# LD_DRV_CK.net
KiCad netlist of a schematic drawn in EAGLE
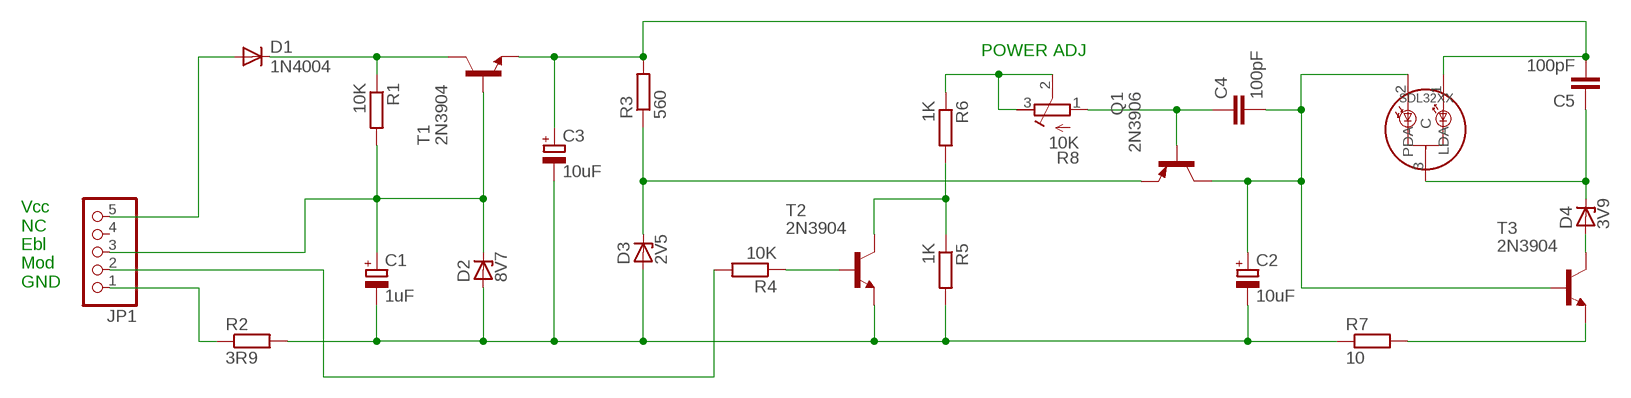
[diagram p0: schematic, sheet 1]

(export (version "E")
  (design (tool "Eeschema 10.0.6"))
  (components
    (comp (ref "C1")
      (value "1uF")
      (footprint "eagle-import:E2,5-6E")
      (libsource (lib "eagle-import") (part "CPOL-EUE2,5-6E"))
    )
    (comp (ref "C2")
      (value "10uF")
      (footprint "eagle-import:E2,5-6E")
      (libsource (lib "eagle-import") (part "CPOL-EUE2,5-6E"))
    )
    (comp (ref "C3")
      (value "10uF")
      (footprint "eagle-import:E2,5-6E")
      (libsource (lib "eagle-import") (part "CPOL-EUE2,5-6E"))
    )
    (comp (ref "C4")
      (value "100pF")
      (footprint "eagle-import:C025-030X050")
      (libsource (lib "eagle-import") (part "C-EU025-030X050"))
    )
    (comp (ref "C5")
      (value "100pF")
      (footprint "eagle-import:C025-030X050")
      (libsource (lib "eagle-import") (part "C-EU025-030X050"))
    )
    (comp (ref "D1")
      (value "1N4004")
      (footprint "eagle-import:DO41-10")
      (libsource (lib "eagle-import") (part "1N4004"))
    )
    (comp (ref "D2")
      (value "8V7")
      (footprint "eagle-import:ZDIO-10")
      (libsource (lib "eagle-import") (part "ZENER-DIODEZD-10"))
    )
    (comp (ref "D3")
      (value "2V5")
      (footprint "eagle-import:ZDIO-10")
      (libsource (lib "eagle-import") (part "ZENER-DIODEZD-10"))
    )
    (comp (ref "D4")
      (value "3V9")
      (footprint "eagle-import:ZDIO-10")
      (libsource (lib "eagle-import") (part "ZENER-DIODEZD-10"))
    )
    (comp (ref "JP1")
      (value "PINHD-1X5/90")
      (footprint "eagle-import:1X05_90")
      (libsource (lib "eagle-import") (part "PINHD-1X5/90"))
    )
    (comp (ref "Q1")
      (value "2N3906")
      (footprint "eagle-import:TO92")
      (libsource (lib "eagle-import") (part "2N3906"))
    )
    (comp (ref "R1")
      (value "10K")
      (footprint "eagle-import:0207_10")
      (libsource (lib "eagle-import") (part "R-EU_0207/10"))
    )
    (comp (ref "R2")
      (value "3R9")
      (footprint "eagle-import:0207_10")
      (libsource (lib "eagle-import") (part "R-EU_0207/10"))
    )
    (comp (ref "R3")
      (value "560")
      (footprint "eagle-import:0207_10")
      (libsource (lib "eagle-import") (part "R-EU_0207/10"))
    )
    (comp (ref "R4")
      (value "10K")
      (footprint "eagle-import:0207_10")
      (libsource (lib "eagle-import") (part "R-EU_0207/10"))
    )
    (comp (ref "R5")
      (value "1K")
      (footprint "eagle-import:0207_10")
      (libsource (lib "eagle-import") (part "R-EU_0207/10"))
    )
    (comp (ref "R6")
      (value "1K")
      (footprint "eagle-import:0207_10")
      (libsource (lib "eagle-import") (part "R-EU_0207/10"))
    )
    (comp (ref "R7")
      (value "10")
      (footprint "eagle-import:0207_10")
      (libsource (lib "eagle-import") (part "R-EU_0207/10"))
    )
    (comp (ref "R8")
      (value "10K")
      (footprint "eagle-import:RTRIM3339P")
      (libsource (lib "eagle-import") (part "R-TRIMM3339P"))
    )
    (comp (ref "SLD32XX_1")
      (value "SLD32XX")
      (footprint "eagle-import:SLD32XXVF")
      (libsource (lib "eagle-import") (part "SLD32XX"))
    )
    (comp (ref "T1")
      (value "2N3904")
      (footprint "eagle-import:TO92")
      (libsource (lib "eagle-import") (part "2N3904"))
    )
    (comp (ref "T2")
      (value "2N3904")
      (footprint "eagle-import:TO92")
      (libsource (lib "eagle-import") (part "2N3904"))
    )
    (comp (ref "T3")
      (value "2N3904")
      (footprint "eagle-import:TO92")
      (libsource (lib "eagle-import") (part "2N3904"))
    )
  )
  (nets
    (net (code "1") (name "Net-(D1-PadA)") (class "Default")
      (node (ref "D1") (pin "A") (pinfunction "A_A") (pintype "passive"))
      (node (ref "JP1") (pin "5") (pinfunction "5_5") (pintype "passive"))
    )
    (net (code "2") (name "Net-(JP1-Pad1)") (class "Default")
      (node (ref "JP1") (pin "1") (pinfunction "1_1") (pintype "passive"))
      (node (ref "R2") (pin "1") (pinfunction "1_1") (pintype "passive"))
    )
    (net (code "3") (name "Net-(JP1-Pad2)") (class "Default")
      (node (ref "JP1") (pin "2") (pinfunction "2_2") (pintype "passive"))
      (node (ref "R4") (pin "2") (pinfunction "2_2") (pintype "passive"))
    )
    (net (code "4") (name "Net-(Q1-B)") (class "Default")
      (node (ref "C4") (pin "1") (pinfunction "1_1") (pintype "passive"))
      (node (ref "Q1") (pin "2") (pinfunction "B_2") (pintype "passive"))
      (node (ref "R8") (pin "1") (pinfunction "A_1") (pintype "passive"))
    )
    (net (code "5") (name "Net-(Q1-C)") (class "Default")
      (node (ref "C2") (pin "+") (pinfunction "+_+") (pintype "passive"))
      (node (ref "C4") (pin "2") (pinfunction "2_2") (pintype "passive"))
      (node (ref "Q1") (pin "1") (pinfunction "C_1") (pintype "passive"))
      (node (ref "SLD32XX_1") (pin "2") (pinfunction "PDA_2") (pintype "input"))
      (node (ref "T3") (pin "2") (pinfunction "B_2") (pintype "passive"))
    )
    (net (code "6") (name "Net-(Q1-E)") (class "Default")
      (node (ref "D3") (pin "C") (pinfunction "C_C") (pintype "passive"))
      (node (ref "Q1") (pin "3") (pinfunction "E_3") (pintype "passive"))
      (node (ref "R3") (pin "1") (pinfunction "1_1") (pintype "passive"))
    )
    (net (code "7") (name "Net-(R8-E)") (class "Default")
      (node (ref "R6") (pin "1") (pinfunction "1_1") (pintype "passive"))
      (node (ref "R8") (pin "2") (pinfunction "S_2") (pintype "passive"))
      (node (ref "R8") (pin "3") (pinfunction "E_3") (pintype "passive"))
    )
    (net (code "8") (name "Net-(SLD32XX_1-C)") (class "Default")
      (node (ref "C5") (pin "1") (pinfunction "1_1") (pintype "passive"))
      (node (ref "D4") (pin "C") (pinfunction "C_C") (pintype "passive"))
      (node (ref "SLD32XX_1") (pin "3") (pinfunction "C_3") (pintype "output"))
    )
    (net (code "9") (name "Net-(SLD32XX_1-LDA)") (class "Default")
      (node (ref "C3") (pin "+") (pinfunction "+_+") (pintype "passive"))
      (node (ref "C5") (pin "2") (pinfunction "2_2") (pintype "passive"))
      (node (ref "R3") (pin "2") (pinfunction "2_2") (pintype "passive"))
      (node (ref "SLD32XX_1") (pin "1") (pinfunction "LDA_1") (pintype "input"))
      (node (ref "T1") (pin "3") (pinfunction "E_3") (pintype "passive"))
    )
    (net (code "10") (name "Net-(T1-B)") (class "Default")
      (node (ref "C1") (pin "+") (pinfunction "+_+") (pintype "passive"))
      (node (ref "D2") (pin "C") (pinfunction "C_C") (pintype "passive"))
      (node (ref "JP1") (pin "3") (pinfunction "3_3") (pintype "passive"))
      (node (ref "R1") (pin "2") (pinfunction "2_2") (pintype "passive"))
      (node (ref "T1") (pin "2") (pinfunction "B_2") (pintype "passive"))
    )
    (net (code "11") (name "Net-(T1-C)") (class "Default")
      (node (ref "D1") (pin "C") (pinfunction "C_C") (pintype "passive"))
      (node (ref "R1") (pin "1") (pinfunction "1_1") (pintype "passive"))
      (node (ref "T1") (pin "1") (pinfunction "C_1") (pintype "passive"))
    )
    (net (code "12") (name "Net-(T2-B)") (class "Default")
      (node (ref "R4") (pin "1") (pinfunction "1_1") (pintype "passive"))
      (node (ref "T2") (pin "2") (pinfunction "B_2") (pintype "passive"))
    )
    (net (code "13") (name "Net-(T2-C)") (class "Default")
      (node (ref "R5") (pin "1") (pinfunction "1_1") (pintype "passive"))
      (node (ref "R6") (pin "2") (pinfunction "2_2") (pintype "passive"))
      (node (ref "T2") (pin "1") (pinfunction "C_1") (pintype "passive"))
    )
    (net (code "14") (name "Net-(T2-E)") (class "Default")
      (node (ref "C1") (pin "-") (pinfunction "-_-") (pintype "passive"))
      (node (ref "C2") (pin "-") (pinfunction "-_-") (pintype "passive"))
      (node (ref "C3") (pin "-") (pinfunction "-_-") (pintype "passive"))
      (node (ref "D2") (pin "A") (pinfunction "A_A") (pintype "passive"))
      (node (ref "D3") (pin "A") (pinfunction "A_A") (pintype "passive"))
      (node (ref "R2") (pin "2") (pinfunction "2_2") (pintype "passive"))
      (node (ref "R5") (pin "2") (pinfunction "2_2") (pintype "passive"))
      (node (ref "R7") (pin "1") (pinfunction "1_1") (pintype "passive"))
      (node (ref "T2") (pin "3") (pinfunction "E_3") (pintype "passive"))
    )
    (net (code "15") (name "Net-(T3-C)") (class "Default")
      (node (ref "D4") (pin "A") (pinfunction "A_A") (pintype "passive"))
      (node (ref "T3") (pin "1") (pinfunction "C_1") (pintype "passive"))
    )
    (net (code "16") (name "Net-(T3-E)") (class "Default")
      (node (ref "R7") (pin "2") (pinfunction "2_2") (pintype "passive"))
      (node (ref "T3") (pin "3") (pinfunction "E_3") (pintype "passive"))
    )
    (net (code "17") (name "unconnected-(JP1-Pad4)") (class "Default")
      (node (ref "JP1") (pin "4") (pinfunction "4_4") (pintype "passive"))
    )
  )
)
